# juares-shield-proto-a1.net
KiCad netlist of a schematic drawn in EAGLE
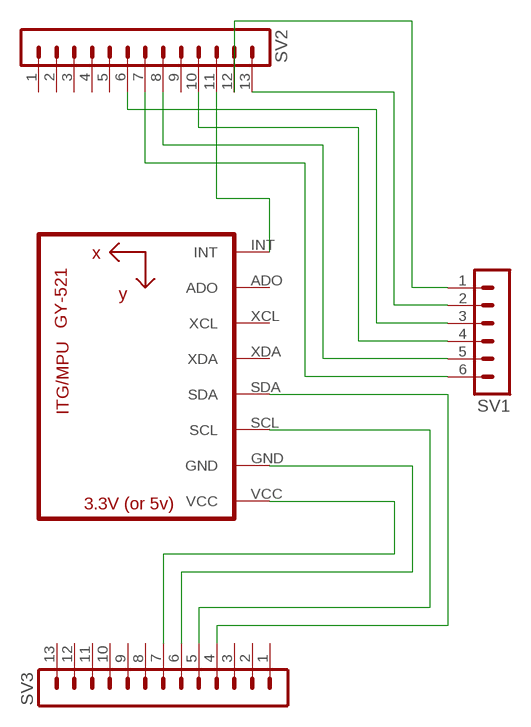
[diagram p0: schematic, sheet 1]

(export (version "E")
  (design (tool "Eeschema 10.0.6"))
  (components
    (comp (ref "SV1")
      (value "MA06-1")
      (footprint "eagle-import:MA06-1")
      (libsource (lib "eagle-import") (part "MA06-1"))
    )
    (comp (ref "SV2")
      (value "MA13-1")
      (footprint "eagle-import:MA13-1")
      (libsource (lib "eagle-import") (part "MA13-1"))
    )
    (comp (ref "SV3")
      (value "MA13-1")
      (footprint "eagle-import:MA13-1")
      (libsource (lib "eagle-import") (part "MA13-1"))
    )
    (comp (ref "U1")
      (value "GY-521MPU6050")
      (footprint "eagle-import:GY-521")
      (libsource (lib "eagle-import") (part "GY-521MPU6050"))
    )
  )
  (nets
    (net (code "1") (name "Net-(SV1-Pad1)") (class "Default")
      (node (ref "SV1") (pin "1") (pinfunction "1_1") (pintype "passive"))
      (node (ref "SV2") (pin "12") (pinfunction "12_12") (pintype "passive"))
    )
    (net (code "2") (name "Net-(SV1-Pad2)") (class "Default")
      (node (ref "SV1") (pin "2") (pinfunction "2_2") (pintype "passive"))
      (node (ref "SV2") (pin "13") (pinfunction "13_13") (pintype "passive"))
    )
    (net (code "3") (name "Net-(SV1-Pad3)") (class "Default")
      (node (ref "SV1") (pin "3") (pinfunction "3_3") (pintype "passive"))
      (node (ref "SV2") (pin "6") (pinfunction "6_6") (pintype "passive"))
    )
    (net (code "4") (name "Net-(SV1-Pad4)") (class "Default")
      (node (ref "SV1") (pin "4") (pinfunction "4_4") (pintype "passive"))
      (node (ref "SV2") (pin "10") (pinfunction "10_10") (pintype "passive"))
    )
    (net (code "5") (name "Net-(SV1-Pad5)") (class "Default")
      (node (ref "SV1") (pin "5") (pinfunction "5_5") (pintype "passive"))
      (node (ref "SV2") (pin "8") (pinfunction "8_8") (pintype "passive"))
    )
    (net (code "6") (name "Net-(SV1-Pad6)") (class "Default")
      (node (ref "SV1") (pin "6") (pinfunction "6_6") (pintype "passive"))
      (node (ref "SV2") (pin "7") (pinfunction "7_7") (pintype "passive"))
    )
    (net (code "7") (name "Net-(SV2-Pad11)") (class "Default")
      (node (ref "SV2") (pin "11") (pinfunction "11_11") (pintype "passive"))
      (node (ref "U1") (pin "INT") (pinfunction "INT_INT") (pintype "bidirectional"))
    )
    (net (code "8") (name "Net-(SV3-Pad4)") (class "Default")
      (node (ref "SV3") (pin "4") (pinfunction "4_4") (pintype "passive"))
      (node (ref "U1") (pin "SDA") (pinfunction "SDA_SDA") (pintype "bidirectional"))
    )
    (net (code "9") (name "Net-(SV3-Pad5)") (class "Default")
      (node (ref "SV3") (pin "5") (pinfunction "5_5") (pintype "passive"))
      (node (ref "U1") (pin "SCL") (pinfunction "SCL_SCL") (pintype "bidirectional"))
    )
    (net (code "10") (name "Net-(SV3-Pad6)") (class "Default")
      (node (ref "SV3") (pin "6") (pinfunction "6_6") (pintype "passive"))
      (node (ref "U1") (pin "GND") (pinfunction "GND_GND") (pintype "bidirectional"))
    )
    (net (code "11") (name "Net-(SV3-Pad7)") (class "Default")
      (node (ref "SV3") (pin "7") (pinfunction "7_7") (pintype "passive"))
      (node (ref "U1") (pin "VCC") (pinfunction "VCC_VCC") (pintype "bidirectional"))
    )
    (net (code "12") (name "unconnected-(SV2-Pad1)") (class "Default")
      (node (ref "SV2") (pin "1") (pinfunction "1_1") (pintype "passive"))
    )
    (net (code "13") (name "unconnected-(SV2-Pad2)") (class "Default")
      (node (ref "SV2") (pin "2") (pinfunction "2_2") (pintype "passive"))
    )
    (net (code "14") (name "unconnected-(SV2-Pad3)") (class "Default")
      (node (ref "SV2") (pin "3") (pinfunction "3_3") (pintype "passive"))
    )
    (net (code "15") (name "unconnected-(SV2-Pad4)") (class "Default")
      (node (ref "SV2") (pin "4") (pinfunction "4_4") (pintype "passive"))
    )
    (net (code "16") (name "unconnected-(SV2-Pad5)") (class "Default")
      (node (ref "SV2") (pin "5") (pinfunction "5_5") (pintype "passive"))
    )
    (net (code "17") (name "unconnected-(SV2-Pad9)") (class "Default")
      (node (ref "SV2") (pin "9") (pinfunction "9_9") (pintype "passive"))
    )
    (net (code "18") (name "unconnected-(SV3-Pad1)") (class "Default")
      (node (ref "SV3") (pin "1") (pinfunction "1_1") (pintype "passive"))
    )
    (net (code "19") (name "unconnected-(SV3-Pad2)") (class "Default")
      (node (ref "SV3") (pin "2") (pinfunction "2_2") (pintype "passive"))
    )
    (net (code "20") (name "unconnected-(SV3-Pad3)") (class "Default")
      (node (ref "SV3") (pin "3") (pinfunction "3_3") (pintype "passive"))
    )
    (net (code "21") (name "unconnected-(SV3-Pad8)") (class "Default")
      (node (ref "SV3") (pin "8") (pinfunction "8_8") (pintype "passive"))
    )
    (net (code "22") (name "unconnected-(SV3-Pad9)") (class "Default")
      (node (ref "SV3") (pin "9") (pinfunction "9_9") (pintype "passive"))
    )
    (net (code "23") (name "unconnected-(SV3-Pad10)") (class "Default")
      (node (ref "SV3") (pin "10") (pinfunction "10_10") (pintype "passive"))
    )
    (net (code "24") (name "unconnected-(SV3-Pad11)") (class "Default")
      (node (ref "SV3") (pin "11") (pinfunction "11_11") (pintype "passive"))
    )
    (net (code "25") (name "unconnected-(SV3-Pad12)") (class "Default")
      (node (ref "SV3") (pin "12") (pinfunction "12_12") (pintype "passive"))
    )
    (net (code "26") (name "unconnected-(SV3-Pad13)") (class "Default")
      (node (ref "SV3") (pin "13") (pinfunction "13_13") (pintype "passive"))
    )
    (net (code "27") (name "unconnected-(U1-PadADO)") (class "Default")
      (node (ref "U1") (pin "ADO") (pinfunction "ADO_ADO") (pintype "bidirectional"))
    )
    (net (code "28") (name "unconnected-(U1-PadXCL)") (class "Default")
      (node (ref "U1") (pin "XCL") (pinfunction "XCL_XCL") (pintype "bidirectional"))
    )
    (net (code "29") (name "unconnected-(U1-PadXDA)") (class "Default")
      (node (ref "U1") (pin "XDA") (pinfunction "XDA_XDA") (pintype "bidirectional"))
    )
  )
)
